# optocouplers.net
KiCad netlist of a schematic drawn in Altium Designer
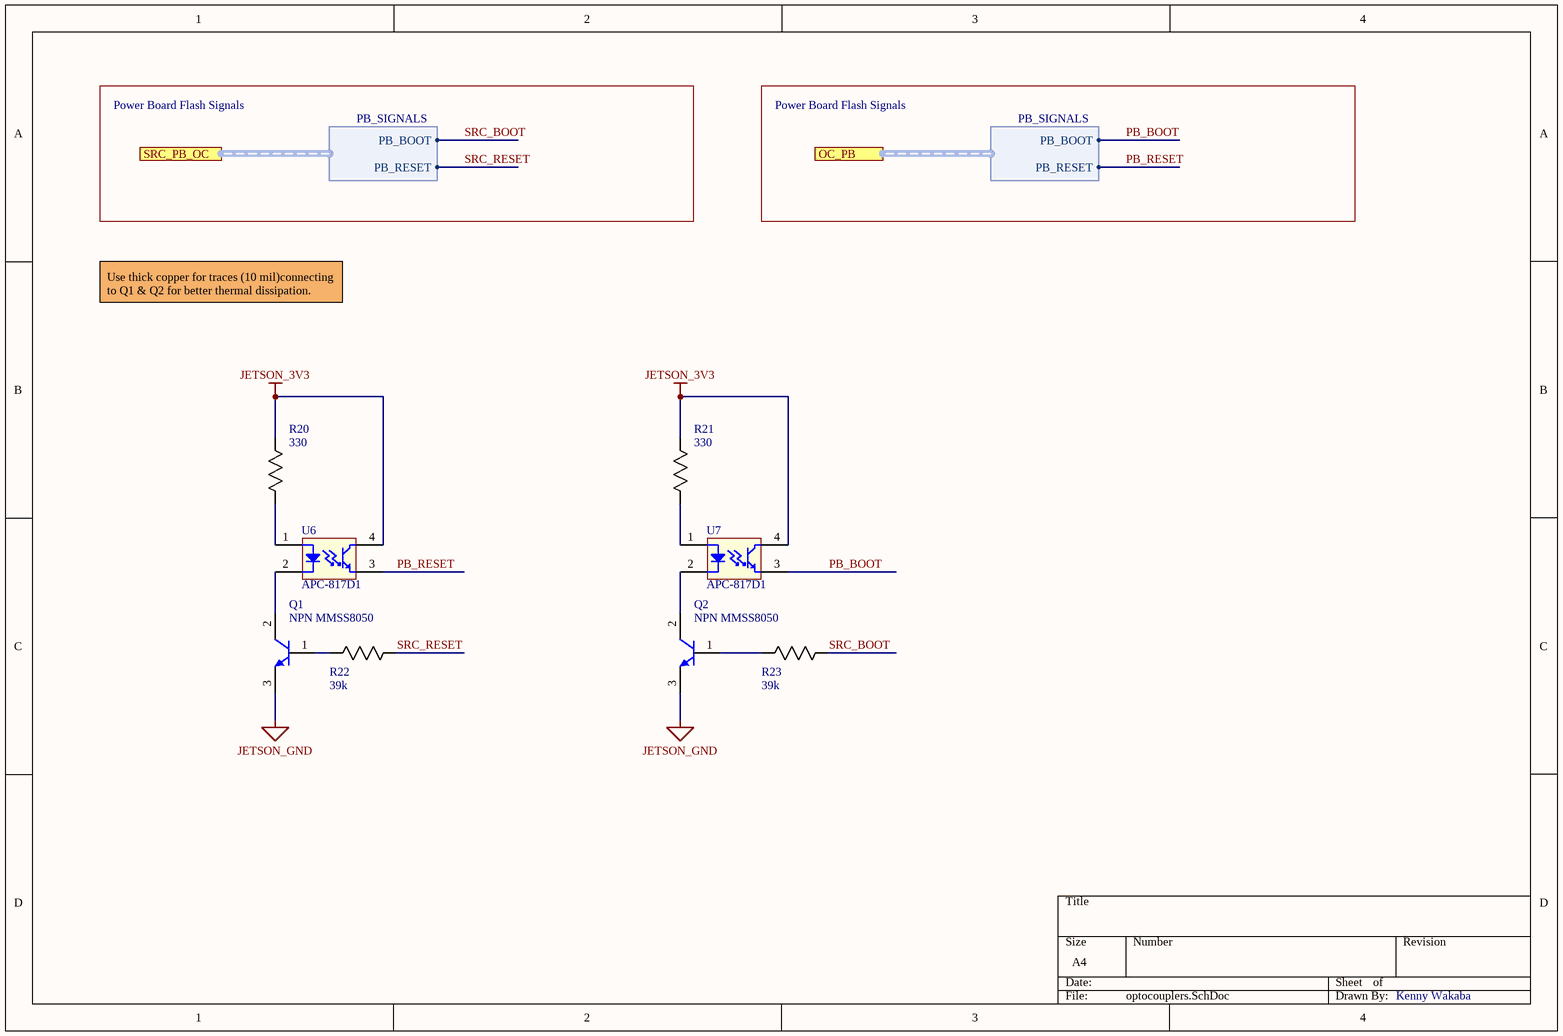
[diagram p0: optocouplers.SchDoc]

(export (version "E")
  (design (tool "Eeschema 10.0.6"))
  (components
    (comp (ref "Q1")
      (value "NPN MMSS8050")
      (footprint "SOT95P237X112-3N")
      (description "Bipolar (BJT) Transistor NPN 25 V 1.5 A 100MHz 625 mW Surface Mount SOT-23")
      (fields (field (name "PART NUMBER") "N_BJT MMSS8050"))
      (libsource (lib "Transistor_Library") (part "NPN MMSS8050"))
    )
    (comp (ref "Q2")
      (value "NPN MMSS8050")
      (footprint "SOT95P237X112-3N")
      (description "Bipolar (BJT) Transistor NPN 25 V 1.5 A 100MHz 625 mW Surface Mount SOT-23")
      (fields (field (name "PART NUMBER") "N_BJT MMSS8050"))
      (libsource (lib "Transistor_Library") (part "NPN MMSS8050"))
    )
    (comp (ref "R20")
      (value "330")
      (footprint "0603")
      (description "Default Resistor Symbol")
      (fields (field (name "TOLERANCE") "5%") (field (name "PART NUMBER") "RES 330.0 1/8W - 5%"))
      (libsource (lib "Resistor_Library") (part "RES_DEFAULT"))
    )
    (comp (ref "R21")
      (value "330")
      (footprint "0603")
      (description "Default Resistor Symbol")
      (fields (field (name "TOLERANCE") "5%") (field (name "PART NUMBER") "RES 330.0 1/8W - 5%"))
      (libsource (lib "Resistor_Library") (part "RES_DEFAULT"))
    )
    (comp (ref "R22")
      (value "39k")
      (footprint "0603")
      (description "Default Resistor Symbol")
      (fields (field (name "TOLERANCE") "1%") (field (name "PART NUMBER") "RES 39k 1/8W"))
      (libsource (lib "Resistor_Library") (part "RES_DEFAULT"))
    )
    (comp (ref "R23")
      (value "39k")
      (footprint "0603")
      (description "Default Resistor Symbol")
      (fields (field (name "TOLERANCE") "1%") (field (name "PART NUMBER") "RES 39k 1/8W"))
      (libsource (lib "Resistor_Library") (part "RES_DEFAULT"))
    )
    (comp (ref "U6")
      (value "APC-817D1")
      (footprint "APC-817D1")
      (description "DIP4, DC Input, Optocoupler")
      (libsource (lib "IC_Library") (part "APC-817D1"))
    )
    (comp (ref "U7")
      (value "APC-817D1")
      (footprint "APC-817D1")
      (description "DIP4, DC Input, Optocoupler")
      (libsource (lib "IC_Library") (part "APC-817D1"))
    )
  )
  (nets
    (net (code "2") (name "/PB_BOOT") (class "Default")
      (node (ref "U7") (pin "3") (pinfunction "3_3") (pintype "passive"))
    )
    (net (code "3") (name "/PB_RESET") (class "Default")
      (node (ref "U6") (pin "3") (pinfunction "3_3") (pintype "passive"))
    )
    (net (code "4") (name "/SRC_BOOT") (class "Default")
      (node (ref "R23") (pin "1") (pinfunction "R1_1") (pintype "passive"))
    )
    (net (code "5") (name "/SRC_RESET") (class "Default")
      (node (ref "R22") (pin "1") (pinfunction "R1_1") (pintype "passive"))
    )
    (net (code "7") (name "JETSON_3V3") (class "Default")
      (node (ref "R20") (pin "2") (pinfunction "R2_2") (pintype "passive"))
      (node (ref "R21") (pin "2") (pinfunction "R2_2") (pintype "passive"))
      (node (ref "U6") (pin "4") (pinfunction "4_4") (pintype "passive"))
      (node (ref "U7") (pin "4") (pinfunction "4_4") (pintype "passive"))
    )
    (net (code "8") (name "JETSON_GND") (class "Default")
      (node (ref "Q1") (pin "3") (pinfunction "E_3") (pintype "passive"))
      (node (ref "Q2") (pin "3") (pinfunction "E_3") (pintype "passive"))
    )
    (net (code "9") (name "Net-(Q1-B)") (class "Default")
      (node (ref "Q1") (pin "1") (pinfunction "B_1") (pintype "passive"))
      (node (ref "R22") (pin "2") (pinfunction "R2_2") (pintype "passive"))
    )
    (net (code "10") (name "Net-(Q1-C)") (class "Default")
      (node (ref "Q1") (pin "2") (pinfunction "C_2") (pintype "passive"))
      (node (ref "U6") (pin "2") (pinfunction "2_2") (pintype "passive"))
    )
    (net (code "11") (name "Net-(Q2-B)") (class "Default")
      (node (ref "Q2") (pin "1") (pinfunction "B_1") (pintype "passive"))
      (node (ref "R23") (pin "2") (pinfunction "R2_2") (pintype "passive"))
    )
    (net (code "12") (name "Net-(Q2-C)") (class "Default")
      (node (ref "Q2") (pin "2") (pinfunction "C_2") (pintype "passive"))
      (node (ref "U7") (pin "2") (pinfunction "2_2") (pintype "passive"))
    )
    (net (code "13") (name "Net-(R20-R1)") (class "Default")
      (node (ref "R20") (pin "1") (pinfunction "R1_1") (pintype "passive"))
      (node (ref "U6") (pin "1") (pinfunction "1_1") (pintype "passive"))
    )
    (net (code "14") (name "Net-(R21-R1)") (class "Default")
      (node (ref "R21") (pin "1") (pinfunction "R1_1") (pintype "passive"))
      (node (ref "U7") (pin "1") (pinfunction "1_1") (pintype "passive"))
    )
  )
)
